# 1-Schematic_PI_Attenuator_SMD_ENCLOSURE.net
KiCad netlist of a schematic drawn in EasyEDA
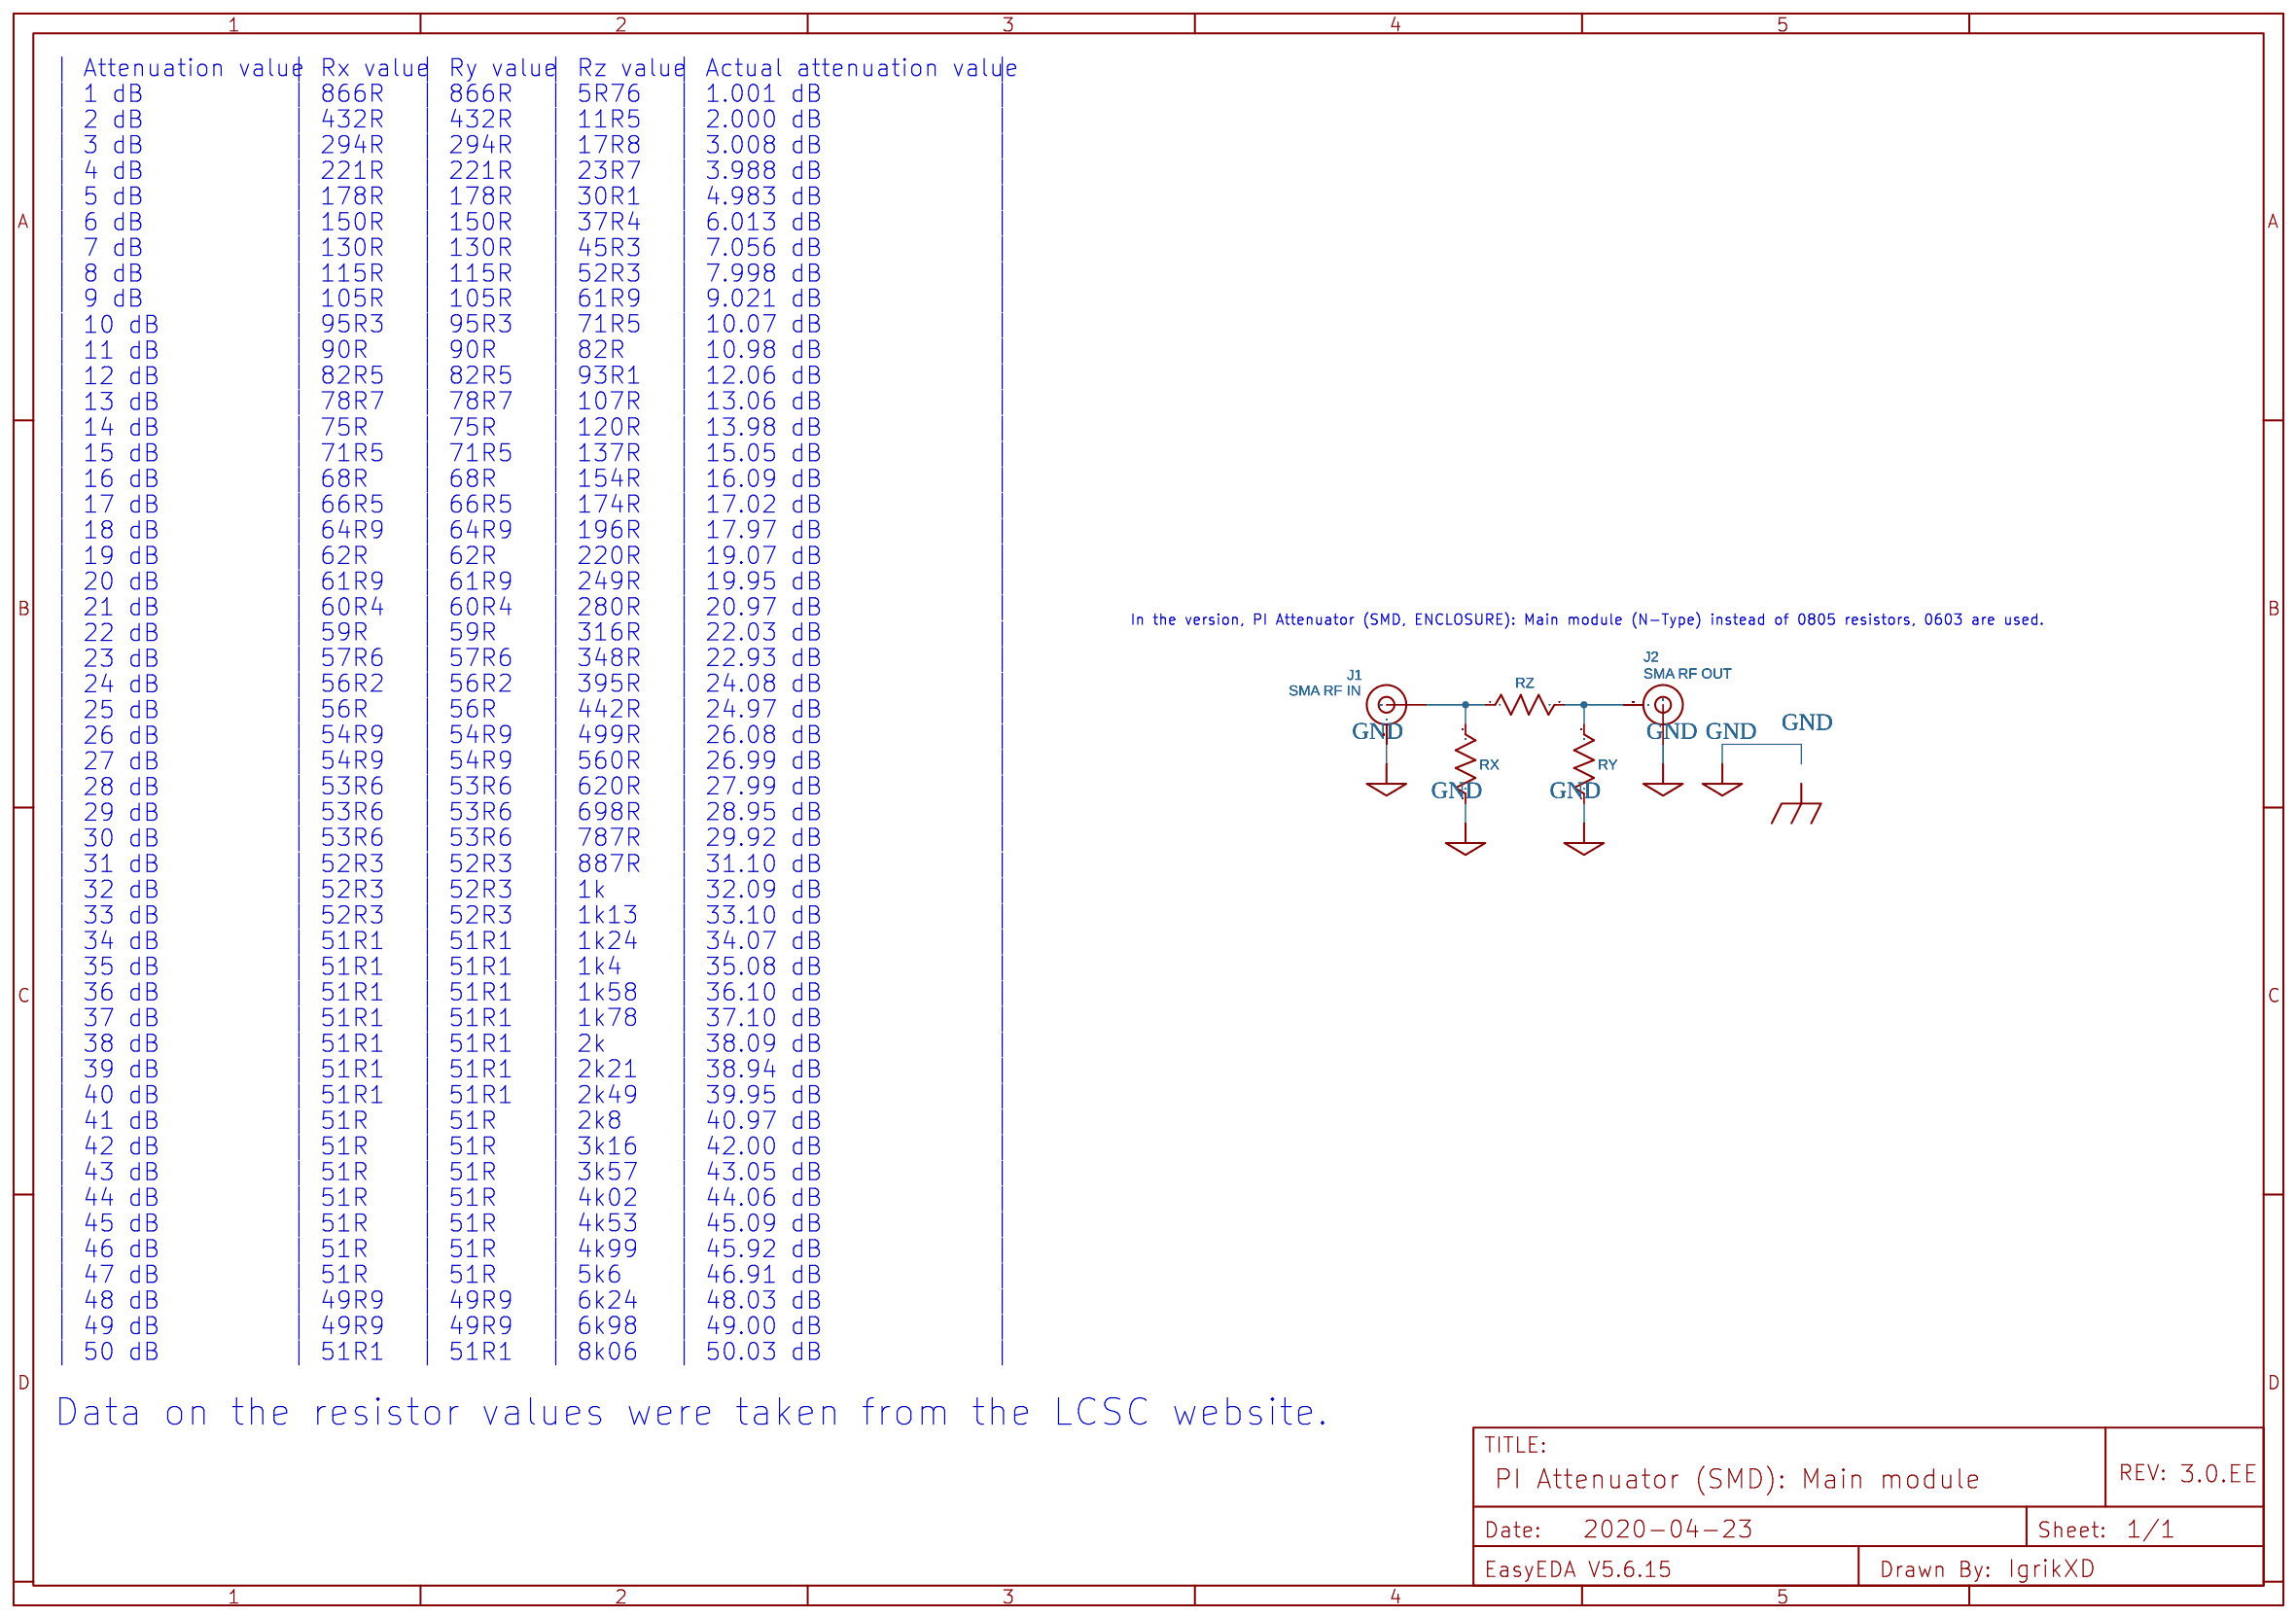
[diagram p0: schematic sheet]

(export (version "E")
  (design (tool "Eeschema 10.0.6"))
  (components
    (comp (ref "J1")
      (value "SMA RF IN")
      (fields
        (field (name "BOM_Manufacturer Part") "ANKX01.0093")
        (field (name "BOM_Supplier Part") "C129604")
      )
      (libsource (lib "") (part "Unknown_700_370"))
    )
    (comp (ref "J2")
      (value "SMA RF OUT")
      (fields
        (field (name "BOM_Manufacturer Part") "ANKX01.0093")
        (field (name "BOM_Supplier Part") "C129604")
      )
      (libsource (lib "") (part "Unknown_815_355"))
    )
    (comp (ref "RX")
      (value "CALCULATED")
      (fields (field (name "BOM_Manufacturer Part") "?"))
      (libsource (lib "") (part "Res_0805(1/8W)_US_1"))
    )
    (comp (ref "RY")
      (value "CALCULATED")
      (fields (field (name "BOM_Manufacturer Part") "?"))
      (libsource (lib "") (part "Res_0805(1/8W)_US_2"))
    )
    (comp (ref "RZ")
      (value "CALCULATED")
      (fields (field (name "BOM_Manufacturer Part") "?"))
      (libsource (lib "") (part "Res_0805(1/8W)_US"))
    )
  )
  (nets
    (net (code "1") (name "GND") (class "Default")
      (node (ref "J1") (pin "GND@0") (pinfunction "GND_GND@0") (pintype "unspecified"))
      (node (ref "J1") (pin "GND@1") (pinfunction "GND_GND@1") (pintype "unspecified"))
      (node (ref "J1") (pin "GND@2") (pinfunction "GND_GND@2") (pintype "unspecified"))
      (node (ref "J1") (pin "GND@3") (pinfunction "GND_GND@3") (pintype "unspecified"))
      (node (ref "J2") (pin "SIG") (pinfunction "SIGNAL_SIG") (pintype "unspecified"))
      (node (ref "RX") (pin "1") (pinfunction "1_1") (pintype "unspecified"))
      (node (ref "RY") (pin "1") (pinfunction "1_1") (pintype "unspecified"))
    )
    (net (code "2") (name "Net-(J1-SIGNAL)") (class "Default")
      (node (ref "J1") (pin "SIG") (pinfunction "SIGNAL_SIG") (pintype "unspecified"))
      (node (ref "RX") (pin "2") (pinfunction "2_2") (pintype "unspecified"))
      (node (ref "RZ") (pin "1") (pinfunction "1_1") (pintype "unspecified"))
    )
    (net (code "3") (name "Net-(J2-GND-PadGND@0)") (class "Default")
      (node (ref "J2") (pin "GND@0") (pinfunction "GND_GND@0") (pintype "unspecified"))
      (node (ref "J2") (pin "GND@1") (pinfunction "GND_GND@1") (pintype "unspecified"))
      (node (ref "J2") (pin "GND@2") (pinfunction "GND_GND@2") (pintype "unspecified"))
      (node (ref "J2") (pin "GND@3") (pinfunction "GND_GND@3") (pintype "unspecified"))
      (node (ref "RY") (pin "2") (pinfunction "2_2") (pintype "unspecified"))
      (node (ref "RZ") (pin "2") (pinfunction "2_2") (pintype "unspecified"))
    )
  )
)
